# SCH_NFC-card_2024-10-10.net
KiCad netlist of a schematic drawn in EasyEDA
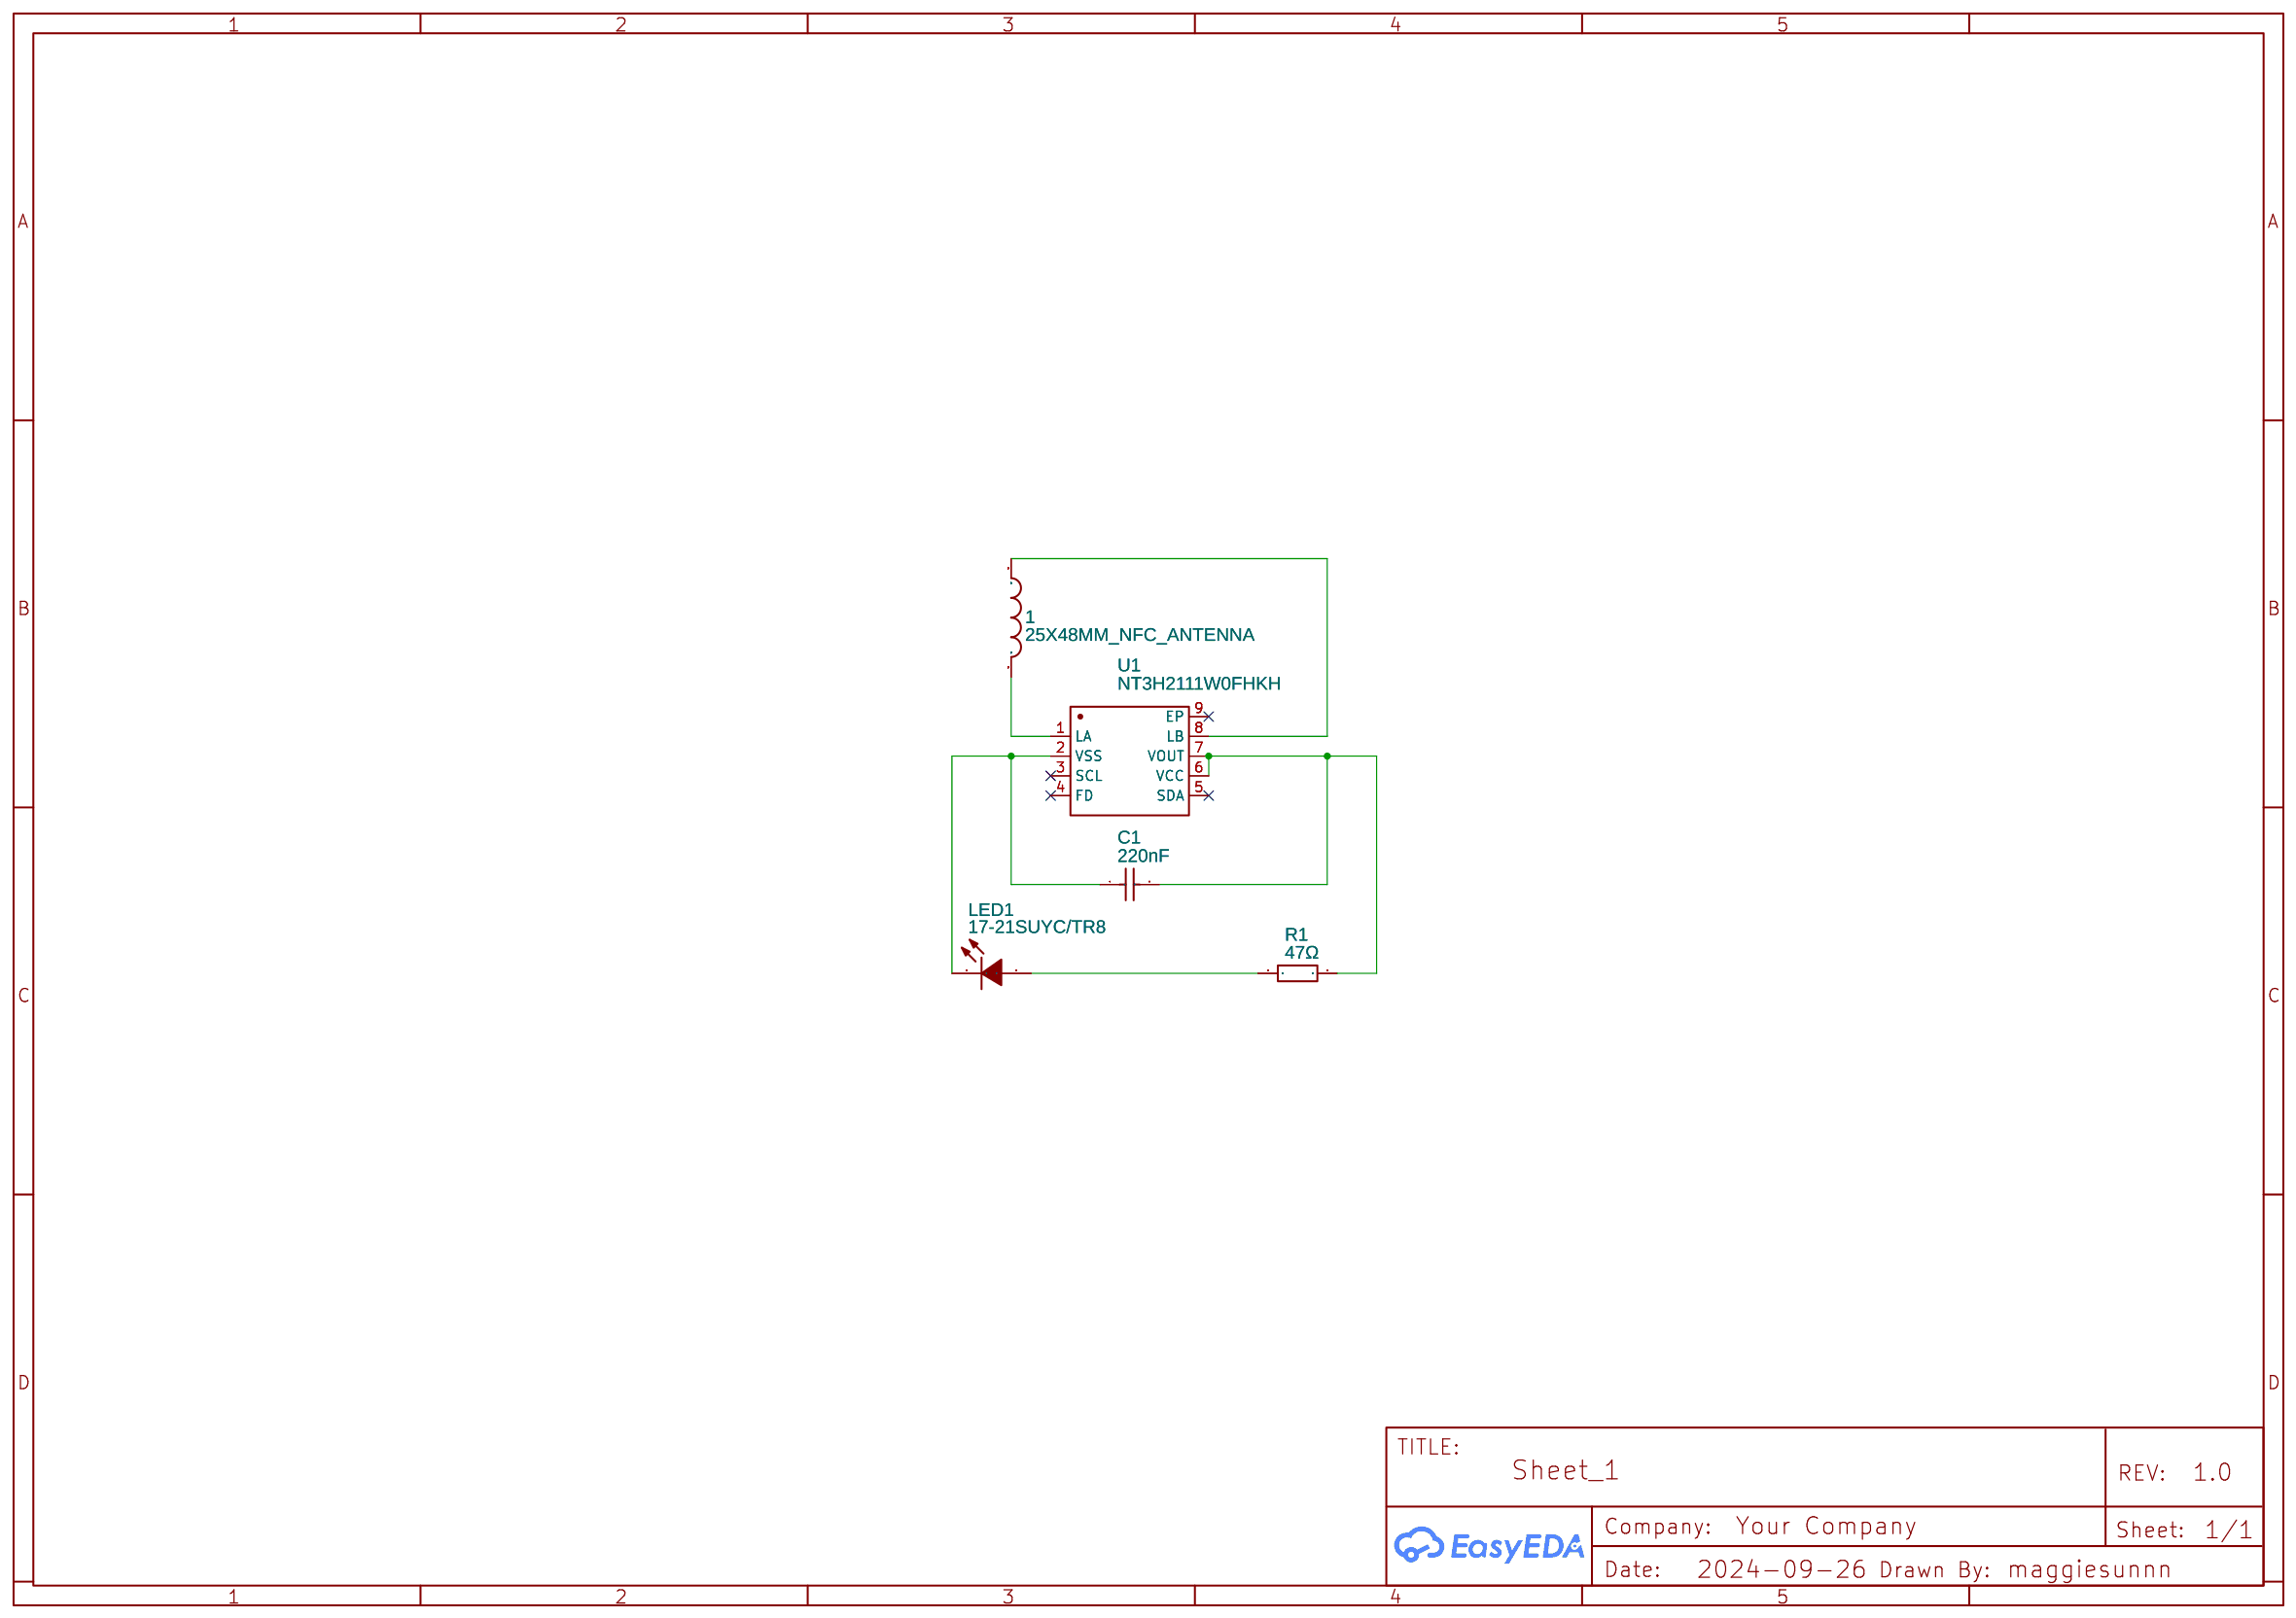
[diagram p0: schematic sheet]

(export (version "E")
  (design (tool "Eeschema 10.0.6"))
  (components
    (comp (ref "1") (value "25X48MM_NFC_ANTENNA") (libsource (lib "") (part "25X48MM_NFC_ANTENNA")))
    (comp (ref "C1")
      (value "220nF")
      (fields
        (field (name "Manufacturer Part") "CL10B224KA8NNNC")
        (field (name "Manufacturer") "SAMSUNG(三星)")
      )
      (libsource (lib "") (part "CL10B224KA8NNNC"))
    )
    (comp (ref "LED1")
      (value "17-21SUYC/TR8")
      (fields (field (name "Manufacturer Part") "KT-0805黄灯") (field (name "Manufacturer") "KENTO"))
      (libsource (lib "") (part "17-21SUYC/TR8"))
    )
    (comp (ref "R1")
      (value "47Ω")
      (fields
        (field (name "Manufacturer Part") "0603WAF470JT5E")
        (field (name "Manufacturer") "UNI-ROYAL(厚声)")
      )
      (libsource (lib "") (part "0603WAF470JT5E"))
    )
    (comp (ref "U1")
      (value "NT3H2111W0FHKH")
      (fields (field (name "Manufacturer") "NXP(恩智浦)"))
      (libsource (lib "") (part "NT3H2111W0FHKH"))
    )
  )
  (nets
    (net (code "1") (name "Net-(LED1-+)") (class "Default")
      (node (ref "LED1") (pin "1") (pinfunction "+_1") (pintype "unspecified"))
      (node (ref "R1") (pin "1") (pinfunction "1_1") (pintype "input"))
    )
    (net (code "2") (name "Net-(LED1--)") (class "Default")
      (node (ref "C1") (pin "1") (pinfunction "1_1") (pintype "input"))
      (node (ref "LED1") (pin "2") (pinfunction "-_2") (pintype "unspecified"))
      (node (ref "U1") (pin "2") (pinfunction "VSS_2") (pintype "unspecified"))
    )
    (net (code "3") (name "Net-(U1-LA)") (class "Default")
      (node (ref "1") (pin "P$2") (pinfunction "P$2_P$2") (pintype "bidirectional"))
      (node (ref "U1") (pin "1") (pinfunction "LA_1") (pintype "unspecified"))
    )
    (net (code "4") (name "Net-(U1-LB)") (class "Default")
      (node (ref "1") (pin "P$1") (pinfunction "P$1_P$1") (pintype "bidirectional"))
      (node (ref "U1") (pin "8") (pinfunction "LB_8") (pintype "unspecified"))
    )
    (net (code "5") (name "Net-(U1-VCC)") (class "Default")
      (node (ref "C1") (pin "2") (pinfunction "2_2") (pintype "input"))
      (node (ref "R1") (pin "2") (pinfunction "2_2") (pintype "input"))
      (node (ref "U1") (pin "6") (pinfunction "VCC_6") (pintype "unspecified"))
      (node (ref "U1") (pin "7") (pinfunction "VOUT_7") (pintype "unspecified"))
    )
    (net (code "6") (name "unconnected-(U1-EP-Pad9)") (class "Default")
      (node (ref "U1") (pin "9") (pinfunction "EP_9") (pintype "unspecified+no_connect"))
    )
    (net (code "7") (name "unconnected-(U1-FD-Pad4)") (class "Default")
      (node (ref "U1") (pin "4") (pinfunction "FD_4") (pintype "unspecified+no_connect"))
    )
    (net (code "8") (name "unconnected-(U1-SCL-Pad3)") (class "Default")
      (node (ref "U1") (pin "3") (pinfunction "SCL_3") (pintype "unspecified+no_connect"))
    )
    (net (code "9") (name "unconnected-(U1-SDA-Pad5)") (class "Default")
      (node (ref "U1") (pin "5") (pinfunction "SDA_5") (pintype "unspecified+no_connect"))
    )
  )
)
